# power.net
KiCad netlist of a schematic drawn in Altium Designer
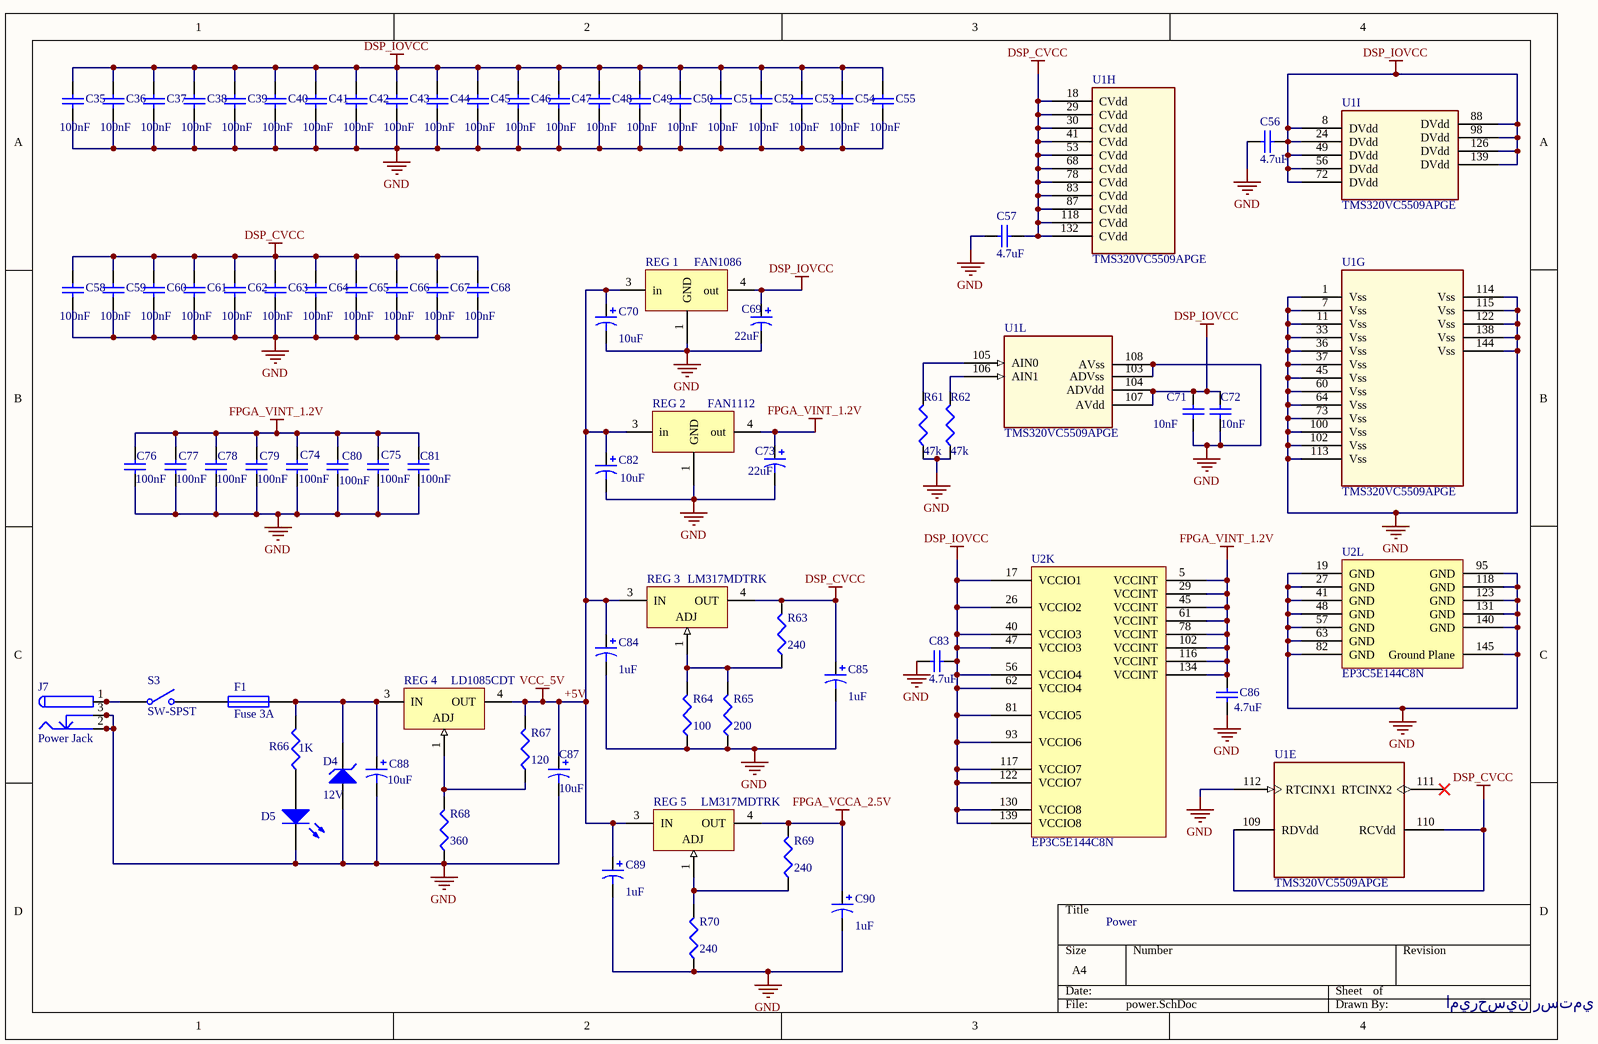
[diagram p0: power.SchDoc]

(export (version "E")
  (design (tool "Eeschema 10.0.6"))
  (components
    (comp (ref "C35")
      (value "100nF")
      (footprint "1608[0603]")
      (description "Capacitor")
      (fields (field (name "PUBLISHER") "Altium Limited"))
      (libsource (lib "Miscellaneous Devices") (part "Cap Semi"))
    )
    (comp (ref "C36")
      (value "100nF")
      (footprint "1608[0603]")
      (description "Capacitor")
      (fields (field (name "PUBLISHER") "Altium Limited"))
      (libsource (lib "Miscellaneous Devices") (part "Cap Semi"))
    )
    (comp (ref "C37")
      (value "100nF")
      (footprint "1608[0603]")
      (description "Capacitor")
      (fields (field (name "PUBLISHER") "Altium Limited"))
      (libsource (lib "Miscellaneous Devices") (part "Cap Semi"))
    )
    (comp (ref "C38")
      (value "100nF")
      (footprint "1608[0603]")
      (description "Capacitor")
      (fields (field (name "PUBLISHER") "Altium Limited"))
      (libsource (lib "Miscellaneous Devices") (part "Cap Semi"))
    )
    (comp (ref "C39")
      (value "100nF")
      (footprint "1608[0603]")
      (description "Capacitor")
      (fields (field (name "PUBLISHER") "Altium Limited"))
      (libsource (lib "Miscellaneous Devices") (part "Cap Semi"))
    )
    (comp (ref "C40")
      (value "100nF")
      (footprint "1608[0603]")
      (description "Capacitor")
      (fields (field (name "PUBLISHER") "Altium Limited"))
      (libsource (lib "Miscellaneous Devices") (part "Cap Semi"))
    )
    (comp (ref "C41")
      (value "100nF")
      (footprint "1608[0603]")
      (description "Capacitor")
      (fields (field (name "PUBLISHER") "Altium Limited"))
      (libsource (lib "Miscellaneous Devices") (part "Cap Semi"))
    )
    (comp (ref "C42")
      (value "100nF")
      (footprint "1608[0603]")
      (description "Capacitor")
      (fields (field (name "PUBLISHER") "Altium Limited"))
      (libsource (lib "Miscellaneous Devices") (part "Cap Semi"))
    )
    (comp (ref "C43")
      (value "100nF")
      (footprint "1608[0603]")
      (description "Capacitor")
      (fields (field (name "PUBLISHER") "Altium Limited"))
      (libsource (lib "Miscellaneous Devices") (part "Cap Semi"))
    )
    (comp (ref "C44")
      (value "100nF")
      (footprint "1608[0603]")
      (description "Capacitor")
      (fields (field (name "PUBLISHER") "Altium Limited"))
      (libsource (lib "Miscellaneous Devices") (part "Cap Semi"))
    )
    (comp (ref "C45")
      (value "100nF")
      (footprint "1608[0603]")
      (description "Capacitor")
      (fields (field (name "PUBLISHER") "Altium Limited"))
      (libsource (lib "Miscellaneous Devices") (part "Cap Semi"))
    )
    (comp (ref "C46")
      (value "100nF")
      (footprint "1608[0603]")
      (description "Capacitor")
      (fields (field (name "PUBLISHER") "Altium Limited"))
      (libsource (lib "Miscellaneous Devices") (part "Cap Semi"))
    )
    (comp (ref "C47")
      (value "100nF")
      (footprint "1608[0603]")
      (description "Capacitor")
      (fields (field (name "PUBLISHER") "Altium Limited"))
      (libsource (lib "Miscellaneous Devices") (part "Cap Semi"))
    )
    (comp (ref "C48")
      (value "100nF")
      (footprint "1608[0603]")
      (description "Capacitor")
      (fields (field (name "PUBLISHER") "Altium Limited"))
      (libsource (lib "Miscellaneous Devices") (part "Cap Semi"))
    )
    (comp (ref "C49")
      (value "100nF")
      (footprint "1608[0603]")
      (description "Capacitor")
      (fields (field (name "PUBLISHER") "Altium Limited"))
      (libsource (lib "Miscellaneous Devices") (part "Cap Semi"))
    )
    (comp (ref "C50")
      (value "100nF")
      (footprint "1608[0603]")
      (description "Capacitor")
      (fields (field (name "PUBLISHER") "Altium Limited"))
      (libsource (lib "Miscellaneous Devices") (part "Cap Semi"))
    )
    (comp (ref "C51")
      (value "100nF")
      (footprint "1608[0603]")
      (description "Capacitor")
      (fields (field (name "PUBLISHER") "Altium Limited"))
      (libsource (lib "Miscellaneous Devices") (part "Cap Semi"))
    )
    (comp (ref "C52")
      (value "100nF")
      (footprint "1608[0603]")
      (description "Capacitor")
      (fields (field (name "PUBLISHER") "Altium Limited"))
      (libsource (lib "Miscellaneous Devices") (part "Cap Semi"))
    )
    (comp (ref "C53")
      (value "100nF")
      (footprint "1608[0603]")
      (description "Capacitor")
      (fields (field (name "PUBLISHER") "Altium Limited"))
      (libsource (lib "Miscellaneous Devices") (part "Cap Semi"))
    )
    (comp (ref "C54")
      (value "100nF")
      (footprint "1608[0603]")
      (description "Capacitor")
      (fields (field (name "PUBLISHER") "Altium Limited"))
      (libsource (lib "Miscellaneous Devices") (part "Cap Semi"))
    )
    (comp (ref "C55")
      (value "100nF")
      (footprint "1608[0603]")
      (description "Capacitor")
      (fields (field (name "PUBLISHER") "Altium Limited"))
      (libsource (lib "Miscellaneous Devices") (part "Cap Semi"))
    )
    (comp (ref "C56")
      (value "4.7uF")
      (footprint "1608[0603]")
      (description "Capacitor")
      (fields (field (name "PUBLISHER") "Altium Limited"))
      (libsource (lib "Miscellaneous Devices") (part "Cap Semi"))
    )
    (comp (ref "C57")
      (value "4.7uF")
      (footprint "1608[0603]")
      (description "Capacitor")
      (fields (field (name "PUBLISHER") "Altium Limited"))
      (libsource (lib "Miscellaneous Devices") (part "Cap Semi"))
    )
    (comp (ref "C58")
      (value "100nF")
      (footprint "1608[0603]")
      (description "Capacitor")
      (fields (field (name "PUBLISHER") "Altium Limited"))
      (libsource (lib "Miscellaneous Devices") (part "Cap Semi"))
    )
    (comp (ref "C59")
      (value "100nF")
      (footprint "1608[0603]")
      (description "Capacitor")
      (fields (field (name "PUBLISHER") "Altium Limited"))
      (libsource (lib "Miscellaneous Devices") (part "Cap Semi"))
    )
    (comp (ref "C60")
      (value "100nF")
      (footprint "1608[0603]")
      (description "Capacitor")
      (fields (field (name "PUBLISHER") "Altium Limited"))
      (libsource (lib "Miscellaneous Devices") (part "Cap Semi"))
    )
    (comp (ref "C61")
      (value "100nF")
      (footprint "1608[0603]")
      (description "Capacitor")
      (fields (field (name "PUBLISHER") "Altium Limited"))
      (libsource (lib "Miscellaneous Devices") (part "Cap Semi"))
    )
    (comp (ref "C62")
      (value "100nF")
      (footprint "1608[0603]")
      (description "Capacitor")
      (fields (field (name "PUBLISHER") "Altium Limited"))
      (libsource (lib "Miscellaneous Devices") (part "Cap Semi"))
    )
    (comp (ref "C63")
      (value "100nF")
      (footprint "1608[0603]")
      (description "Capacitor")
      (fields (field (name "PUBLISHER") "Altium Limited"))
      (libsource (lib "Miscellaneous Devices") (part "Cap Semi"))
    )
    (comp (ref "C64")
      (value "100nF")
      (footprint "1608[0603]")
      (description "Capacitor")
      (fields (field (name "PUBLISHER") "Altium Limited"))
      (libsource (lib "Miscellaneous Devices") (part "Cap Semi"))
    )
    (comp (ref "C65")
      (value "100nF")
      (footprint "1608[0603]")
      (description "Capacitor")
      (fields (field (name "PUBLISHER") "Altium Limited"))
      (libsource (lib "Miscellaneous Devices") (part "Cap Semi"))
    )
    (comp (ref "C66")
      (value "100nF")
      (footprint "1608[0603]")
      (description "Capacitor")
      (fields (field (name "PUBLISHER") "Altium Limited"))
      (libsource (lib "Miscellaneous Devices") (part "Cap Semi"))
    )
    (comp (ref "C67")
      (value "100nF")
      (footprint "1608[0603]")
      (description "Capacitor")
      (fields (field (name "PUBLISHER") "Altium Limited"))
      (libsource (lib "Miscellaneous Devices") (part "Cap Semi"))
    )
    (comp (ref "C68")
      (value "100nF")
      (footprint "1608[0603]")
      (description "Capacitor")
      (fields (field (name "PUBLISHER") "Altium Limited"))
      (libsource (lib "Miscellaneous Devices") (part "Cap Semi"))
    )
    (comp (ref "C69")
      (value "22uF")
      (footprint "C1206")
      (description "Polarized Capacitor (Tantalium)")
      (fields (field (name "PUBLISHER") "Altium Limited"))
      (libsource (lib "Miscellaneous Devices") (part "Cap Pol3"))
    )
    (comp (ref "C70")
      (value "10uF")
      (footprint "C1206")
      (description "Polarized Capacitor (Tantalium)")
      (fields (field (name "PUBLISHER") "Altium Limited"))
      (libsource (lib "Miscellaneous Devices") (part "Cap Pol3"))
    )
    (comp (ref "C71")
      (value "10nF")
      (footprint "1608[0603]")
      (description "Capacitor")
      (fields (field (name "Comment") "1onF") (field (name "PUBLISHER") "Altium Limited"))
      (libsource (lib "Miscellaneous Devices") (part "Cap Semi"))
    )
    (comp (ref "C72")
      (value "10nF")
      (footprint "1608[0603]")
      (description "Capacitor")
      (fields (field (name "PUBLISHER") "Altium Limited"))
      (libsource (lib "Miscellaneous Devices") (part "Cap Semi"))
    )
    (comp (ref "C73")
      (value "22uF")
      (footprint "C1206")
      (description "Polarized Capacitor (Tantalium)")
      (fields (field (name "PUBLISHER") "Altium Limited"))
      (libsource (lib "Miscellaneous Devices") (part "Cap Pol3"))
    )
    (comp (ref "C74")
      (value "100nF")
      (footprint "1608[0603]")
      (description "Capacitor")
      (fields (field (name "PUBLISHER") "Altium Limited"))
      (libsource (lib "Miscellaneous Devices") (part "Cap Semi"))
    )
    (comp (ref "C75")
      (value "100nF")
      (footprint "1608[0603]")
      (description "Capacitor")
      (fields (field (name "PUBLISHER") "Altium Limited"))
      (libsource (lib "Miscellaneous Devices") (part "Cap Semi"))
    )
    (comp (ref "C76")
      (value "100nF")
      (footprint "1608[0603]")
      (description "Capacitor")
      (fields (field (name "PUBLISHER") "Altium Limited"))
      (libsource (lib "Miscellaneous Devices") (part "Cap Semi"))
    )
    (comp (ref "C77")
      (value "100nF")
      (footprint "1608[0603]")
      (description "Capacitor")
      (fields (field (name "PUBLISHER") "Altium Limited"))
      (libsource (lib "Miscellaneous Devices") (part "Cap Semi"))
    )
    (comp (ref "C78")
      (value "100nF")
      (footprint "1608[0603]")
      (description "Capacitor")
      (fields (field (name "PUBLISHER") "Altium Limited"))
      (libsource (lib "Miscellaneous Devices") (part "Cap Semi"))
    )
    (comp (ref "C79")
      (value "100nF")
      (footprint "1608[0603]")
      (description "Capacitor")
      (fields (field (name "PUBLISHER") "Altium Limited"))
      (libsource (lib "Miscellaneous Devices") (part "Cap Semi"))
    )
    (comp (ref "C80")
      (value "100nF")
      (footprint "1608[0603]")
      (description "Capacitor")
      (fields (field (name "PUBLISHER") "Altium Limited"))
      (libsource (lib "Miscellaneous Devices") (part "Cap Semi"))
    )
    (comp (ref "C81")
      (value "100nF")
      (footprint "1608[0603]")
      (description "Capacitor")
      (fields (field (name "PUBLISHER") "Altium Limited"))
      (libsource (lib "Miscellaneous Devices") (part "Cap Semi"))
    )
    (comp (ref "C82")
      (value "10uF")
      (footprint "C1206")
      (description "Polarized Capacitor (Tantalium)")
      (fields (field (name "PUBLISHER") "Altium Limited"))
      (libsource (lib "Miscellaneous Devices") (part "Cap Pol3"))
    )
    (comp (ref "C83")
      (value "4.7uF")
      (footprint "1608[0603]")
      (description "Capacitor")
      (fields (field (name "PUBLISHER") "Altium Limited"))
      (libsource (lib "Miscellaneous Devices") (part "Cap Semi"))
    )
    (comp (ref "C84")
      (value "1uF")
      (footprint "C1206")
      (description "Polarized Capacitor (Tantalium)")
      (fields (field (name "PUBLISHER") "Altium Limited"))
      (libsource (lib "Miscellaneous Devices") (part "Cap Pol3"))
    )
    (comp (ref "C85")
      (value "1uF")
      (footprint "C1206")
      (description "Polarized Capacitor (Tantalium)")
      (fields (field (name "PUBLISHER") "Altium Limited"))
      (libsource (lib "Miscellaneous Devices") (part "Cap Pol3"))
    )
    (comp (ref "C86")
      (value "4.7uF")
      (footprint "1608[0603]")
      (description "Capacitor")
      (fields (field (name "PUBLISHER") "Altium Limited"))
      (libsource (lib "Miscellaneous Devices") (part "Cap Semi"))
    )
    (comp (ref "C87")
      (value "10uF")
      (footprint "C1206")
      (description "Polarized Capacitor (Tantalium)")
      (fields (field (name "Comment") "22uF") (field (name "PUBLISHER") "Altium Limited"))
      (libsource (lib "Miscellaneous Devices") (part "Cap Pol3"))
    )
    (comp (ref "C88")
      (value "10uF")
      (footprint "C1206")
      (description "Polarized Capacitor (Tantalium)")
      (fields (field (name "PUBLISHER") "Altium Limited"))
      (libsource (lib "Miscellaneous Devices") (part "Cap Pol3"))
    )
    (comp (ref "C89")
      (value "1uF")
      (footprint "C1206")
      (description "Polarized Capacitor (Tantalium)")
      (fields (field (name "PUBLISHER") "Altium Limited"))
      (libsource (lib "Miscellaneous Devices") (part "Cap Pol3"))
    )
    (comp (ref "C90")
      (value "1uF")
      (footprint "C1206")
      (description "Polarized Capacitor (Tantalium)")
      (fields (field (name "PUBLISHER") "Altium Limited"))
      (libsource (lib "Miscellaneous Devices") (part "Cap Pol3"))
    )
    (comp (ref "D4")
      (value "12V")
      (footprint "MELF-D3512-1405")
      (description "Silicon Zener Diode")
      (fields (field (name "PUBLISHER") "Altium Limited"))
      (libsource (lib "Vishay Lite-On Discrete Diode") (part "DL4742A"))
    )
    (comp (ref "D5")
      (value "LED green")
      (footprint "1.6X0.8X0.4")
      (description "Typical BLUE SiC LED")
      (fields (field (name "PUBLISHER") "Altium Limited"))
      (libsource (lib "Miscellaneous Devices") (part "LED3"))
    )
    (comp (ref "F1")
      (value "Fuse 3A")
      (footprint "2012[0805]")
      (description "Fuse")
      (fields (field (name "PUBLISHER") "Altium Limited"))
      (libsource (lib "Miscellaneous Devices") (part "Fuse 1"))
    )
    (comp (ref "J7")
      (value "Power Jack")
      (footprint "KLD-0202")
      (description "Low Voltage Power Supply Connector")
      (fields (field (name "PUBLISHER") "Altium Limited"))
      (libsource (lib "Miscellaneous Connectors") (part "PWR2.5"))
    )
    (comp (ref "R61")
      (value "47k")
      (footprint "J1-0603")
      (description "Resistor")
      (fields (field (name "Comment") "47K") (field (name "PUBLISHER") "Altium Limited"))
      (libsource (lib "Miscellaneous Devices") (part "Res3"))
    )
    (comp (ref "R62")
      (value "47k")
      (footprint "J1-0603")
      (description "Resistor")
      (fields (field (name "PUBLISHER") "Altium Limited"))
      (libsource (lib "Miscellaneous Devices") (part "Res3"))
    )
    (comp (ref "R63")
      (value "240")
      (footprint "J1-0603")
      (description "Resistor")
      (fields (field (name "PUBLISHER") "Altium Limited"))
      (libsource (lib "Miscellaneous Devices") (part "Res3"))
    )
    (comp (ref "R64")
      (value "100")
      (footprint "J1-0603")
      (description "Resistor")
      (fields (field (name "PUBLISHER") "Altium Limited"))
      (libsource (lib "Miscellaneous Devices") (part "Res3"))
    )
    (comp (ref "R65")
      (value "200")
      (footprint "J1-0603")
      (description "Resistor")
      (fields (field (name "PUBLISHER") "Altium Limited"))
      (libsource (lib "Miscellaneous Devices") (part "Res3"))
    )
    (comp (ref "R66")
      (value "1K")
      (footprint "J1-0603")
      (description "Resistor")
      (fields (field (name "PUBLISHER") "Altium Limited"))
      (libsource (lib "Miscellaneous Devices") (part "Res3"))
    )
    (comp (ref "R67")
      (value "120")
      (footprint "J1-0603")
      (description "Resistor")
      (fields (field (name "PUBLISHER") "Altium Limited"))
      (libsource (lib "Miscellaneous Devices") (part "Res3"))
    )
    (comp (ref "R68")
      (value "360")
      (footprint "J1-0603")
      (description "Resistor")
      (fields (field (name "PUBLISHER") "Altium Limited"))
      (libsource (lib "Miscellaneous Devices") (part "Res3"))
    )
    (comp (ref "R69")
      (value "240")
      (footprint "J1-0603")
      (description "Resistor")
      (fields (field (name "PUBLISHER") "Altium Limited"))
      (libsource (lib "Miscellaneous Devices") (part "Res3"))
    )
    (comp (ref "R70")
      (value "240")
      (footprint "J1-0603")
      (description "Resistor")
      (fields (field (name "PUBLISHER") "Altium Limited"))
      (libsource (lib "Miscellaneous Devices") (part "Res3"))
    )
    (comp (ref "REG 1")
      (value "FAN1086")
      (footprint "369A-13")
      (description "1.5A, 3.3V Fixed Low Dropout Linear Regulator")
      (libsource (lib "FAN1086") (part "FAN1086"))
    )
    (comp (ref "REG 2")
      (value "FAN1112")
      (footprint "369A-13")
      (description "1A 1.2V Low Dropout Linear Regulator")
      (libsource (lib "FAN1112") (part "FAN1112"))
    )
    (comp (ref "REG 3")
      (value "LM317MDTRK")
      (footprint "369A-13")
      (description "Three-Terminal Adjustable Output Positive Voltage Regulator")
      (fields (field (name "PUBLISHER") "Altium Limited"))
      (libsource (lib "ON Semi Power Mgt Voltage Regulator") (part "LM317MDTRK"))
    )
    (comp (ref "REG 4")
      (value "LD1085CDT")
      (footprint "369A-13")
      (description "Three-Terminal Adjustable Output Positive Voltage Regulator")
      (fields (field (name "PUBLISHER") "Altium Limited"))
      (libsource (lib "ON Semi Power Mgt Voltage Regulator") (part "LM317MDT"))
    )
    (comp (ref "REG 5")
      (value "LM317MDTRK")
      (footprint "369A-13")
      (description "Three-Terminal Adjustable Output Positive Voltage Regulator")
      (fields (field (name "PUBLISHER") "Altium Limited"))
      (libsource (lib "ON Semi Power Mgt Voltage Regulator") (part "LM317MDTRK"))
    )
    (comp (ref "S3")
      (value "SW-SPST")
      (footprint "DIP_SW_1")
      (description "Single-Pole, Single-Throw Switch")
      (fields (field (name "PUBLISHER") "Altium Limited"))
      (libsource (lib "Miscellaneous Devices") (part "SW-SPST"))
    )
    (comp (ref "U1")
      (value "TMS320VC5509APGE")
      (footprint "TMSVC5509APGA")
      (libsource (lib "TMSVC5509APGE") (part "TMS320VC5509APGE"))
    )
    (comp (ref "U2")
      (value "EP3C5E144C8N")
      (footprint "EQFP144_N")
      (fields (field (name "PUBLISHER") "Altium Limited"))
      (libsource (lib "Altera Cyclone III") (part "EP3C5E144C8N"))
    )
  )
  (nets
    (net (code "1") (name "DSP_CVCC") (class "Default")
      (node (ref "C57") (pin "2") (pinfunction "2_2") (pintype "passive"))
      (node (ref "C58") (pin "1") (pinfunction "1_1") (pintype "passive"))
      (node (ref "C59") (pin "1") (pinfunction "1_1") (pintype "passive"))
      (node (ref "C60") (pin "1") (pinfunction "1_1") (pintype "passive"))
      (node (ref "C61") (pin "1") (pinfunction "1_1") (pintype "passive"))
      (node (ref "C62") (pin "1") (pinfunction "1_1") (pintype "passive"))
      (node (ref "C63") (pin "1") (pinfunction "1_1") (pintype "passive"))
      (node (ref "C64") (pin "1") (pinfunction "1_1") (pintype "passive"))
      (node (ref "C65") (pin "1") (pinfunction "1_1") (pintype "passive"))
      (node (ref "C66") (pin "1") (pinfunction "1_1") (pintype "passive"))
      (node (ref "C67") (pin "1") (pinfunction "1_1") (pintype "passive"))
      (node (ref "C68") (pin "1") (pinfunction "1_1") (pintype "passive"))
      (node (ref "C85") (pin "1") (pinfunction "1_1") (pintype "passive"))
      (node (ref "R63") (pin "2") (pinfunction "2_2") (pintype "passive"))
      (node (ref "REG 3") (pin "4") (pinfunction "OUT_4") (pintype "power_in"))
      (node (ref "U1") (pin "109") (pinfunction "RDVdd_109") (pintype "power_in"))
      (node (ref "U1") (pin "110") (pinfunction "RCVdd_110") (pintype "power_in"))
      (node (ref "U1") (pin "118") (pinfunction "CVdd_118") (pintype "power_in"))
      (node (ref "U1") (pin "132") (pinfunction "CVdd_132") (pintype "power_in"))
      (node (ref "U1") (pin "18") (pinfunction "CVdd_18") (pintype "power_in"))
      (node (ref "U1") (pin "29") (pinfunction "CVdd_29") (pintype "power_in"))
      (node (ref "U1") (pin "30") (pinfunction "CVdd_30") (pintype "power_in"))
      (node (ref "U1") (pin "41") (pinfunction "CVdd_41") (pintype "power_in"))
      (node (ref "U1") (pin "53") (pinfunction "CVdd_53") (pintype "power_in"))
      (node (ref "U1") (pin "68") (pinfunction "CVdd_68") (pintype "power_in"))
      (node (ref "U1") (pin "78") (pinfunction "CVdd_78") (pintype "power_in"))
      (node (ref "U1") (pin "83") (pinfunction "CVdd_83") (pintype "power_in"))
      (node (ref "U1") (pin "87") (pinfunction "CVdd_87") (pintype "power_in"))
    )
    (net (code "2") (name "DSP_IOVCC") (class "Default")
      (node (ref "C35") (pin "1") (pinfunction "1_1") (pintype "passive"))
      (node (ref "C36") (pin "1") (pinfunction "1_1") (pintype "passive"))
      (node (ref "C37") (pin "1") (pinfunction "1_1") (pintype "passive"))
      (node (ref "C38") (pin "1") (pinfunction "1_1") (pintype "passive"))
      (node (ref "C39") (pin "1") (pinfunction "1_1") (pintype "passive"))
      (node (ref "C40") (pin "1") (pinfunction "1_1") (pintype "passive"))
      (node (ref "C41") (pin "1") (pinfunction "1_1") (pintype "passive"))
      (node (ref "C42") (pin "1") (pinfunction "1_1") (pintype "passive"))
      (node (ref "C43") (pin "1") (pinfunction "1_1") (pintype "passive"))
      (node (ref "C44") (pin "1") (pinfunction "1_1") (pintype "passive"))
      (node (ref "C45") (pin "1") (pinfunction "1_1") (pintype "passive"))
      (node (ref "C46") (pin "1") (pinfunction "1_1") (pintype "passive"))
      (node (ref "C47") (pin "1") (pinfunction "1_1") (pintype "passive"))
      (node (ref "C48") (pin "1") (pinfunction "1_1") (pintype "passive"))
      (node (ref "C49") (pin "1") (pinfunction "1_1") (pintype "passive"))
      (node (ref "C50") (pin "1") (pinfunction "1_1") (pintype "passive"))
      (node (ref "C51") (pin "1") (pinfunction "1_1") (pintype "passive"))
      (node (ref "C52") (pin "1") (pinfunction "1_1") (pintype "passive"))
      (node (ref "C53") (pin "1") (pinfunction "1_1") (pintype "passive"))
      (node (ref "C54") (pin "1") (pinfunction "1_1") (pintype "passive"))
      (node (ref "C55") (pin "1") (pinfunction "1_1") (pintype "passive"))
      (node (ref "C56") (pin "2") (pinfunction "2_2") (pintype "passive"))
      (node (ref "C69") (pin "1") (pinfunction "1_1") (pintype "passive"))
      (node (ref "C71") (pin "1") (pinfunction "1_1") (pintype "passive"))
      (node (ref "C72") (pin "1") (pinfunction "1_1") (pintype "passive"))
      (node (ref "C83") (pin "1") (pinfunction "1_1") (pintype "passive"))
      (node (ref "REG 1") (pin "4") (pinfunction "out_4") (pintype "passive"))
      (node (ref "U1") (pin "104") (pinfunction "ADVdd_104") (pintype "power_in"))
      (node (ref "U1") (pin "107") (pinfunction "AVdd_107") (pintype "power_in"))
      (node (ref "U1") (pin "126") (pinfunction "DVdd_126") (pintype "power_in"))
      (node (ref "U1") (pin "139") (pinfunction "DVdd_139") (pintype "power_in"))
      (node (ref "U1") (pin "24") (pinfunction "DVdd_24") (pintype "power_in"))
      (node (ref "U1") (pin "49") (pinfunction "DVdd_49") (pintype "power_in"))
      (node (ref "U1") (pin "56") (pinfunction "DVdd_56") (pintype "power_in"))
      (node (ref "U1") (pin "72") (pinfunction "DVdd_72") (pintype "power_in"))
      (node (ref "U1") (pin "8") (pinfunction "DVdd_8") (pintype "power_in"))
      (node (ref "U1") (pin "88") (pinfunction "DVdd_88") (pintype "power_in"))
      (node (ref "U1") (pin "98") (pinfunction "DVdd_98") (pintype "power_in"))
      (node (ref "U2") (pin "117") (pinfunction "VCCIO7_117") (pintype "power_in"))
      (node (ref "U2") (pin "122") (pinfunction "VCCIO7_122") (pintype "power_in"))
      (node (ref "U2") (pin "130") (pinfunction "VCCIO8_130") (pintype "power_in"))
      (node (ref "U2") (pin "139") (pinfunction "VCCIO8_139") (pintype "power_in"))
      (node (ref "U2") (pin "17") (pinfunction "VCCIO1_17") (pintype "power_in"))
      (node (ref "U2") (pin "26") (pinfunction "VCCIO2_26") (pintype "power_in"))
      (node (ref "U2") (pin "40") (pinfunction "VCCIO3_40") (pintype "power_in"))
      (node (ref "U2") (pin "47") (pinfunction "VCCIO3_47") (pintype "power_in"))
      (node (ref "U2") (pin "56") (pinfunction "VCCIO4_56") (pintype "power_in"))
      (node (ref "U2") (pin "62") (pinfunction "VCCIO4_62") (pintype "power_in"))
      (node (ref "U2") (pin "81") (pinfunction "VCCIO5_81") (pintype "power_in"))
      (node (ref "U2") (pin "93") (pinfunction "VCCIO6_93") (pintype "power_in"))
    )
    (net (code "3") (name "FPGA_VCCA_2.5V") (class "Default")
      (node (ref "C90") (pin "1") (pinfunction "1_1") (pintype "passive"))
      (node (ref "R69") (pin "2") (pinfunction "2_2") (pintype "passive"))
      (node (ref "REG 5") (pin "4") (pinfunction "OUT_4") (pintype "power_in"))
    )
    (net (code "4") (name "FPGA_VINT_1.2V") (class "Default")
      (node (ref "C73") (pin "1") (pinfunction "1_1") (pintype "passive"))
      (node (ref "C74") (pin "1") (pinfunction "1_1") (pintype "passive"))
      (node (ref "C75") (pin "1") (pinfunction "1_1") (pintype "passive"))
      (node (ref "C76") (pin "1") (pinfunction "1_1") (pintype "passive"))
      (node (ref "C77") (pin "1") (pinfunction "1_1") (pintype "passive"))
      (node (ref "C78") (pin "1") (pinfunction "1_1") (pintype "passive"))
      (node (ref "C79") (pin "1") (pinfunction "1_1") (pintype "passive"))
      (node (ref "C80") (pin "1") (pinfunction "1_1") (pintype "passive"))
      (node (ref "C81") (pin "1") (pinfunction "1_1") (pintype "passive"))
      (node (ref "C86") (pin "2") (pinfunction "2_2") (pintype "passive"))
      (node (ref "REG 2") (pin "4") (pinfunction "out_4") (pintype "passive"))
      (node (ref "U2") (pin "102") (pinfunction "VCCINT_102") (pintype "power_in"))
      (node (ref "U2") (pin "116") (pinfunction "VCCINT_116") (pintype "power_in"))
      (node (ref "U2") (pin "134") (pinfunction "VCCINT_134") (pintype "power_in"))
      (node (ref "U2") (pin "29") (pinfunction "VCCINT_29") (pintype "power_in"))
      (node (ref "U2") (pin "45") (pinfunction "VCCINT_45") (pintype "power_in"))
      (node (ref "U2") (pin "5") (pinfunction "VCCINT_5") (pintype "power_in"))
      (node (ref "U2") (pin "61") (pinfunction "VCCINT_61") (pintype "power_in"))
      (node (ref "U2") (pin "78") (pinfunction "VCCINT_78") (pintype "power_in"))
    )
    (net (code "5") (name "GND") (class "Default")
      (node (ref "C35") (pin "2") (pinfunction "2_2") (pintype "passive"))
      (node (ref "C36") (pin "2") (pinfunction "2_2") (pintype "passive"))
      (node (ref "C37") (pin "2") (pinfunction "2_2") (pintype "passive"))
      (node (ref "C38") (pin "2") (pinfunction "2_2") (pintype "passive"))
      (node (ref "C39") (pin "2") (pinfunction "2_2") (pintype "passive"))
      (node (ref "C40") (pin "2") (pinfunction "2_2") (pintype "passive"))
      (node (ref "C41") (pin "2") (pinfunction "2_2") (pintype "passive"))
      (node (ref "C42") (pin "2") (pinfunction "2_2") (pintype "passive"))
      (node (ref "C43") (pin "2") (pinfunction "2_2") (pintype "passive"))
      (node (ref "C44") (pin "2") (pinfunction "2_2") (pintype "passive"))
      (node (ref "C45") (pin "2") (pinfunction "2_2") (pintype "passive"))
      (node (ref "C46") (pin "2") (pinfunction "2_2") (pintype "passive"))
      (node (ref "C47") (pin "2") (pinfunction "2_2") (pintype "passive"))
      (node (ref "C48") (pin "2") (pinfunction "2_2") (pintype "passive"))
      (node (ref "C49") (pin "2") (pinfunction "2_2") (pintype "passive"))
      (node (ref "C50") (pin "2") (pinfunction "2_2") (pintype "passive"))
      (node (ref "C51") (pin "2") (pinfunction "2_2") (pintype "passive"))
      (node (ref "C52") (pin "2") (pinfunction "2_2") (pintype "passive"))
      (node (ref "C53") (pin "2") (pinfunction "2_2") (pintype "passive"))
      (node (ref "C54") (pin "2") (pinfunction "2_2") (pintype "passive"))
      (node (ref "C55") (pin "2") (pinfunction "2_2") (pintype "passive"))
      (node (ref "C56") (pin "1") (pinfunction "1_1") (pintype "passive"))
      (node (ref "C57") (pin "1") (pinfunction "1_1") (pintype "passive"))
      (node (ref "C58") (pin "2") (pinfunction "2_2") (pintype "passive"))
      (node (ref "C59") (pin "2") (pinfunction "2_2") (pintype "passive"))
      (node (ref "C60") (pin "2") (pinfunction "2_2") (pintype "passive"))
      (node (ref "C61") (pin "2") (pinfunction "2_2") (pintype "passive"))
      (node (ref "C62") (pin "2") (pinfunction "2_2") (pintype "passive"))
      (node (ref "C63") (pin "2") (pinfunction "2_2") (pintype "passive"))
      (node (ref "C64") (pin "2") (pinfunction "2_2") (pintype "passive"))
      (node (ref "C65") (pin "2") (pinfunction "2_2") (pintype "passive"))
      (node (ref "C66") (pin "2") (pinfunction "2_2") (pintype "passive"))
      (node (ref "C67") (pin "2") (pinfunction "2_2") (pintype "passive"))
      (node (ref "C68") (pin "2") (pinfunction "2_2") (pintype "passive"))
      (node (ref "C69") (pin "2") (pinfunction "2_2") (pintype "passive"))
      (node (ref "C70") (pin "2") (pinfunction "2_2") (pintype "passive"))
      (node (ref "C71") (pin "2") (pinfunction "2_2") (pintype "passive"))
      (node (ref "C72") (pin "2") (pinfunction "2_2") (pintype "passive"))
      (node (ref "C73") (pin "2") (pinfunction "2_2") (pintype "passive"))
      (node (ref "C74") (pin "2") (pinfunction "2_2") (pintype "passive"))
      (node (ref "C75") (pin "2") (pinfunction "2_2") (pintype "passive"))
      (node (ref "C76") (pin "2") (pinfunction "2_2") (pintype "passive"))
      (node (ref "C77") (pin "2") (pinfunction "2_2") (pintype "passive"))
      (node (ref "C78") (pin "2") (pinfunction "2_2") (pintype "passive"))
      (node (ref "C79") (pin "2") (pinfunction "2_2") (pintype "passive"))
      (node (ref "C80") (pin "2") (pinfunction "2_2") (pintype "passive"))
      (node (ref "C81") (pin "2") (pinfunction "2_2") (pintype "passive"))
      (node (ref "C82") (pin "2") (pinfunction "2_2") (pintype "passive"))
      (node (ref "C83") (pin "2") (pinfunction "2_2") (pintype "passive"))
      (node (ref "C84") (pin "2") (pinfunction "2_2") (pintype "passive"))
      (node (ref "C85") (pin "2") (pinfunction "2_2") (pintype "passive"))
      (node (ref "C86") (pin "1") (pinfunction "1_1") (pintype "passive"))
      (node (ref "C87") (pin "2") (pinfunction "2_2") (pintype "passive"))
      (node (ref "C88") (pin "2") (pinfunction "2_2") (pintype "passive"))
      (node (ref "C89") (pin "2") (pinfunction "2_2") (pintype "passive"))
      (node (ref "C90") (pin "2") (pinfunction "2_2") (pintype "passive"))
      (node (ref "D4") (pin "1") (pinfunction "A_1") (pintype "passive"))
      (node (ref "D5") (pin "2") (pinfunction "K_2") (pintype "passive"))
      (node (ref "J7") (pin "2") (pinfunction "2_2") (pintype "power_in"))
      (node (ref "J7") (pin "2A") (pinfunction "2A_2A") (pintype "power_in"))
      (node (ref "J7") (pin "2B") (pinfunction "2B_2B") (pintype "power_in"))
      (node (ref "J7") (pin "3") (pinfunction "3_3") (pintype "power_in"))
      (node (ref "J7") (pin "3A") (pinfunction "3A_3A") (pintype "power_in"))
      (node (ref "J7") (pin "3B") (pinfunction "3B_3B") (pintype "power_in"))
      (node (ref "R61") (pin "1") (pinfunction "1_1") (pintype "passive"))
      (node (ref "R62") (pin "1") (pinfunction "1_1") (pintype "passive"))
      (node (ref "R64") (pin "1") (pinfunction "1_1") (pintype "passive"))
      (node (ref "R65") (pin "1") (pinfunction "1_1") (pintype "passive"))
      (node (ref "R68") (pin "1") (pinfunction "1_1") (pintype "passive"))
      (node (ref "R70") (pin "1") (pinfunction "1_1") (pintype "passive"))
      (node (ref "REG 1") (pin "1") (pinfunction "GND_1") (pintype "passive"))
      (node (ref "REG 2") (pin "1") (pinfunction "GND_1") (pintype "passive"))
      (node (ref "U1") (pin "1") (pinfunction "Vss_1") (pintype "power_in"))
      (node (ref "U1") (pin "100") (pinfunction "Vss_100") (pintype "power_in"))
      (node (ref "U1") (pin "102") (pinfunction "Vss_102") (pintype "power_in"))
      (node (ref "U1") (pin "103") (pinfunction "ADVss_103") (pintype "power_in"))
      (node (ref "U1") (pin "108") (pinfunction "AVss_108") (pintype "power_in"))
      (node (ref "U1") (pin "11") (pinfunction "Vss_11") (pintype "power_in"))
      (node (ref "U1") (pin "112") (pinfunction "RTCINX1_112") (pintype "input"))
      (node (ref "U1") (pin "113") (pinfunction "Vss_113") (pintype "power_in"))
      (node (ref "U1") (pin "114") (pinfunction "Vss_114") (pintype "power_in"))
      (node (ref "U1") (pin "115") (pinfunction "Vss_115") (pintype "power_in"))
      (node (ref "U1") (pin "122") (pinfunction "Vss_122") (pintype "power_in"))
      (node (ref "U1") (pin "138") (pinfunction "Vss_138") (pintype "power_in"))
      (node (ref "U1") (pin "144") (pinfunction "Vss_144") (pintype "power_in"))
      (node (ref "U1") (pin "33") (pinfunction "Vss_33") (pintype "power_in"))
      (node (ref "U1") (pin "36") (pinfunction "Vss_36") (pintype "power_in"))
      (node (ref "U1") (pin "37") (pinfunction "Vss_37") (pintype "power_in"))
      (node (ref "U1") (pin "45") (pinfunction "Vss_45") (pintype "power_in"))
      (node (ref "U1") (pin "60") (pinfunction "Vss_60") (pintype "power_in"))
      (node (ref "U1") (pin "64") (pinfunction "Vss_64") (pintype "power_in"))
      (node (ref "U1") (pin "7") (pinfunction "Vss_7") (pintype "power_in"))
      (node (ref "U1") (pin "73") (pinfunction "Vss_73") (pintype "power_in"))
      (node (ref "U2") (pin "118") (pinfunction "GND_118") (pintype "power_in"))
      (node (ref "U2") (pin "123") (pinfunction "GND_123") (pintype "power_in"))
      (node (ref "U2") (pin "131") (pinfunction "GND_131") (pintype "power_in"))
      (node (ref "U2") (pin "140") (pinfunction "GND_140") (pintype "power_in"))
      (node (ref "U2") (pin "145") (pinfunction "Ground_Plane_145") (pintype "power_in"))
      (node (ref "U2") (pin "19") (pinfunction "GND_19") (pintype "power_in"))
      (node (ref "U2") (pin "27") (pinfunction "GND_27") (pintype "power_in"))
      (node (ref "U2") (pin "41") (pinfunction "GND_41") (pintype "power_in"))
      (node (ref "U2") (pin "48") (pinfunction "GND_48") (pintype "power_in"))
      (node (ref "U2") (pin "57") (pinfunction "GND_57") (pintype "power_in"))
      (node (ref "U2") (pin "63") (pinfunction "GND_63") (pintype "power_in"))
      (node (ref "U2") (pin "82") (pinfunction "GND_82") (pintype "power_in"))
      (node (ref "U2") (pin "95") (pinfunction "GND_95") (pintype "power_in"))
    )
    (net (code "6") (name "Net-(D4-K)") (class "Default")
      (node (ref "C88") (pin "1") (pinfunction "1_1") (pintype "passive"))
      (node (ref "D4") (pin "2") (pinfunction "K_2") (pintype "passive"))
      (node (ref "F1") (pin "2") (pinfunction "2_2") (pintype "passive"))
      (node (ref "R66") (pin "2") (pinfunction "2_2") (pintype "passive"))
      (node (ref "REG 4") (pin "3") (pinfunction "IN_3") (pintype "power_in"))
    )
    (net (code "7") (name "Net-(D5-A)") (class "Default")
      (node (ref "D5") (pin "1") (pinfunction "A_1") (pintype "passive"))
      (node (ref "R66") (pin "1") (pinfunction "1_1") (pintype "passive"))
    )
    (net (code "8") (name "Net-(REG 3-ADJ)") (class "Default")
      (node (ref "R63") (pin "1") (pinfunction "1_1") (pintype "passive"))
      (node (ref "R64") (pin "2") (pinfunction "2_2") (pintype "passive"))
      (node (ref "R65") (pin "2") (pinfunction "2_2") (pintype "passive"))
      (node (ref "REG 3") (pin "1") (pinfunction "ADJ_1") (pintype "input"))
    )
    (net (code "9") (name "Net-(REG 4-ADJ)") (class "Default")
      (node (ref "R67") (pin "1") (pinfunction "1_1") (pintype "passive"))
      (node (ref "R68") (pin "2") (pinfunction "2_2") (pintype "passive"))
      (node (ref "REG 4") (pin "1") (pinfunction "ADJ_1") (pintype "input"))
    )
    (net (code "10") (name "Net-(REG 5-ADJ)") (class "Default")
      (node (ref "R69") (pin "1") (pinfunction "1_1") (pintype "passive"))
      (node (ref "R70") (pin "2") (pinfunction "2_2") (pintype "passive"))
      (node (ref "REG 5") (pin "1") (pinfunction "ADJ_1") (pintype "input"))
    )
    (net (code "11") (name "Net-(S3-COMMON)") (class "Default")
      (node (ref "J7") (pin "1") (pinfunction "1_1") (pintype "power_in"))
      (node (ref "J7") (pin "1A") (pinfunction "1A_1A") (pintype "power_in"))
      (node (ref "J7") (pin "1B") (pinfunction "1B_1B") (pintype "power_in"))
      (node (ref "S3") (pin "1") (pinfunction "COMMON_1") (pintype "passive"))
    )
    (net (code "12") (name "Net-(S3-NO)") (class "Default")
      (node (ref "F1") (pin "1") (pinfunction "1_1") (pintype "passive"))
      (node (ref "S3") (pin "2") (pinfunction "NO_2") (pintype "passive"))
    )
    (net (code "13") (name "Net-(U1L-AIN0)") (class "Default")
      (node (ref "R61") (pin "2") (pinfunction "2_2") (pintype "passive"))
      (node (ref "U1") (pin "105") (pinfunction "AIN0_105") (pintype "input"))
    )
    (net (code "14") (name "Net-(U1L-AIN1)") (class "Default")
      (node (ref "R62") (pin "2") (pinfunction "2_2") (pintype "passive"))
      (node (ref "U1") (pin "106") (pinfunction "AIN1_106") (pintype "input"))
    )
    (net (code "15") (name "VCC_5V") (class "Default")
      (node (ref "C70") (pin "1") (pinfunction "1_1") (pintype "passive"))
      (node (ref "C82") (pin "1") (pinfunction "1_1") (pintype "passive"))
      (node (ref "C84") (pin "1") (pinfunction "1_1") (pintype "passive"))
      (node (ref "C87") (pin "1") (pinfunction "1_1") (pintype "passive"))
      (node (ref "C89") (pin "1") (pinfunction "1_1") (pintype "passive"))
      (node (ref "R67") (pin "2") (pinfunction "2_2") (pintype "passive"))
      (node (ref "REG 1") (pin "3") (pinfunction "in_3") (pintype "passive"))
      (node (ref "REG 2") (pin "3") (pinfunction "in_3") (pintype "passive"))
      (node (ref "REG 3") (pin "3") (pinfunction "IN_3") (pintype "power_in"))
      (node (ref "REG 4") (pin "4") (pinfunction "OUT_4") (pintype "power_in"))
      (node (ref "REG 5") (pin "3") (pinfunction "IN_3") (pintype "power_in"))
    )
    (net (code "16") (name "unconnected-(U1E-RTCINX2-Pad111)") (class "Default")
      (node (ref "U1") (pin "111") (pinfunction "RTCINX2_111") (pintype "output+no_connect"))
    )
  )
)
